# mcu.net
KiCad netlist of a schematic drawn in Altium Designer
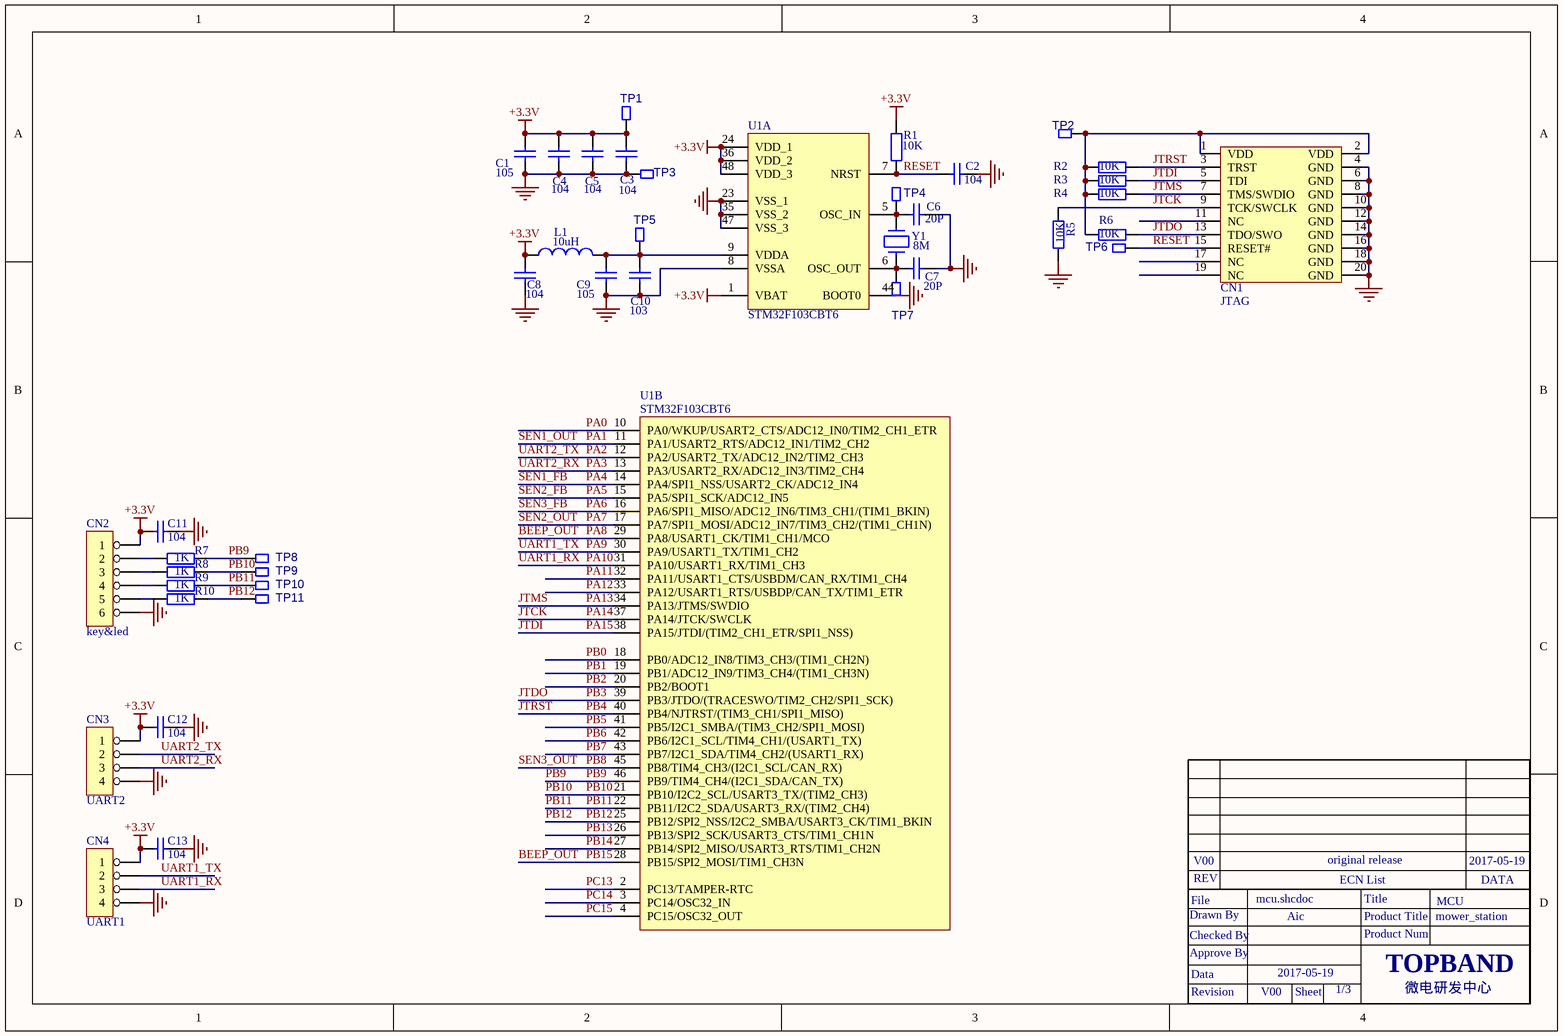
[diagram p0: mcu.SchDoc]

(export (version "E")
  (design (tool "Eeschema 10.0.6"))
  (components
    (comp (ref "C1")
      (value "105")
      (footprint "0603C")
      (libsource (lib "altium-import") (part "root_1_mirrored_Cap(0603)_"))
    )
    (comp (ref "C2")
      (value "104")
      (footprint "0603C")
      (libsource (lib "altium-import") (part "root_0_mirrored_Cap(0603)_"))
    )
    (comp (ref "C3")
      (value "104")
      (footprint "0603C")
      (libsource (lib "altium-import") (part "root_1_mirrored_Cap(0603)_"))
    )
    (comp (ref "C4")
      (value "104")
      (footprint "0603C")
      (libsource (lib "altium-import") (part "root_1_mirrored_Cap(0603)_"))
    )
    (comp (ref "C5")
      (value "104")
      (footprint "0603C")
      (libsource (lib "altium-import") (part "root_1_mirrored_Cap(0603)_"))
    )
    (comp (ref "C6")
      (value "20P")
      (footprint "0603C")
      (libsource (lib "altium-import") (part "root_0_mirrored_Cap(0603)_"))
    )
    (comp (ref "C7")
      (value "20P")
      (footprint "0603C")
      (libsource (lib "altium-import") (part "root_0_mirrored_Cap(0603)_"))
    )
    (comp (ref "C8")
      (value "104")
      (footprint "0603C")
      (libsource (lib "altium-import") (part "root_1_mirrored_Cap(0603)_"))
    )
    (comp (ref "C9")
      (value "105")
      (footprint "0603C")
      (libsource (lib "altium-import") (part "root_1_mirrored_Cap(0603)_"))
    )
    (comp (ref "C10")
      (value "103")
      (footprint "0603C")
      (libsource (lib "altium-import") (part "root_1_mirrored_Cap(0603)_"))
    )
    (comp (ref "C11")
      (value "104")
      (footprint "0603C")
      (libsource (lib "altium-import") (part "root_2_mirrored_Cap(0603)_"))
    )
    (comp (ref "C12")
      (value "104")
      (footprint "0603C")
      (libsource (lib "altium-import") (part "root_2_mirrored_Cap(0603)_"))
    )
    (comp (ref "C13")
      (value "104")
      (footprint "0603C")
      (libsource (lib "altium-import") (part "root_2_mirrored_Cap(0603)_"))
    )
    (comp (ref "CN1") (value "JTAG") (footprint "JTAG_20") (libsource (lib "STM32F429_F746") (part "JTAG")))
    (comp (ref "CN2")
      (value "key&led")
      (footprint "CON6-2.54")
      (description "插座")
      (fields (field (name "PART NUMBER") "6Pin"))
      (libsource (lib "接插器件+IC") (part "6Pin"))
    )
    (comp (ref "CN3")
      (value "UART2")
      (footprint "CON4-2.54")
      (description "插座")
      (fields (field (name "PART NUMBER") "4Pin(2~3.96mm)"))
      (libsource (lib "接插器件+IC") (part "4Pin(2~3.96mm)"))
    )
    (comp (ref "CN4")
      (value "UART1")
      (footprint "CON4-2.54")
      (description "插座")
      (fields (field (name "PART NUMBER") "4Pin(2~3.96mm)"))
      (libsource (lib "接插器件+IC") (part "4Pin(2~3.96mm)"))
    )
    (comp (ref "L1")
      (value "10uH")
      (footprint "0805L-BOT")
      (description "电感")
      (fields (field (name "PART NUMBER") "Inductor(0805)"))
      (libsource (lib "分立器件1") (part "Inductor(0805)"))
    )
    (comp (ref "R1")
      (value "10K")
      (footprint "0603R")
      (description "Resistor")
      (fields (field (name "PUBLISHER") "Altium Limited"))
      (libsource (lib "Miscellaneous Devices") (part "Res2"))
    )
    (comp (ref "R2")
      (value "10K")
      (footprint "0603R")
      (description "Resistor")
      (fields (field (name "PUBLISHER") "Altium Limited"))
      (libsource (lib "") (part "Res2_1"))
    )
    (comp (ref "R3")
      (value "10K")
      (footprint "0603R")
      (description "Resistor")
      (fields (field (name "PUBLISHER") "Altium Limited"))
      (libsource (lib "") (part "Res2_1"))
    )
    (comp (ref "R4")
      (value "10K")
      (footprint "0603R")
      (description "Resistor")
      (fields (field (name "PUBLISHER") "Altium Limited"))
      (libsource (lib "") (part "Res2_1"))
    )
    (comp (ref "R5")
      (value "10K")
      (footprint "0603R")
      (description "Resistor")
      (fields (field (name "PUBLISHER") "Altium Limited"))
      (libsource (lib "Miscellaneous Devices") (part "Res2"))
    )
    (comp (ref "R6")
      (value "10K")
      (footprint "0603R")
      (description "Resistor")
      (fields (field (name "PUBLISHER") "Altium Limited"))
      (libsource (lib "") (part "Res2_1"))
    )
    (comp (ref "R7")
      (value "1K")
      (footprint "0603R")
      (description "电阻器")
      (fields (field (name "PART NUMBER") "Res(0603)"))
      (libsource (lib "分立器件1") (part "Res(0603)"))
    )
    (comp (ref "R8")
      (value "1K")
      (footprint "0603R")
      (description "电阻器")
      (fields (field (name "PART NUMBER") "Res(0603)"))
      (libsource (lib "分立器件1") (part "Res(0603)"))
    )
    (comp (ref "R9")
      (value "1K")
      (footprint "0603R")
      (description "电阻器")
      (fields (field (name "PART NUMBER") "Res(0603)"))
      (libsource (lib "分立器件1") (part "Res(0603)"))
    )
    (comp (ref "R10")
      (value "1K")
      (footprint "0603R")
      (description "电阻器")
      (fields (field (name "PART NUMBER") "Res(0603)"))
      (libsource (lib "分立器件1") (part "Res(0603)"))
    )
    (comp (ref "TP1") (value "TP") (footprint "TEST-0.8MM") (libsource (lib "Topband1") (part "TP")))
    (comp (ref "TP2") (value "TP") (footprint "TEST-0.8MM") (libsource (lib "Topband1") (part "TP")))
    (comp (ref "TP3") (value "TP") (footprint "TEST-0.8MM") (libsource (lib "Topband1") (part "TP")))
    (comp (ref "TP4") (value "TP") (footprint "TEST-0.8MM") (libsource (lib "Topband1") (part "TP")))
    (comp (ref "TP5") (value "TP") (footprint "TEST-0.8MM") (libsource (lib "Topband1") (part "TP")))
    (comp (ref "TP6") (value "TP") (footprint "TEST-0.8MM") (libsource (lib "Topband1") (part "TP")))
    (comp (ref "TP7") (value "TP") (footprint "TEST-0.8MM") (libsource (lib "Topband1") (part "TP")))
    (comp (ref "TP8") (value "TP") (footprint "TEST-0.8MM") (libsource (lib "Topband1") (part "TP")))
    (comp (ref "TP9") (value "TP") (footprint "TEST-0.8MM") (libsource (lib "Topband1") (part "TP")))
    (comp (ref "TP10") (value "TP") (footprint "TEST-0.8MM") (libsource (lib "Topband1") (part "TP")))
    (comp (ref "TP11") (value "TP") (footprint "TEST-0.8MM") (libsource (lib "Topband1") (part "TP")))
    (comp (ref "U1")
      (value "STM32F103CBT6")
      (footprint "LQFP48")
      (description "STM32F103x8")
      (libsource (lib "Schlib1") (part "STM32F103x8"))
    )
    (comp (ref "Y1")
      (value "8M")
      (footprint "XTAL-J")
      (description "晶振")
      (fields (field (name "PART NUMBER") "XTAL-J"))
      (libsource (lib "分立器件1") (part "XTAL-J"))
    )
  )
  (nets
    (net (code "1") (name "+3.3V") (class "Default")
      (node (ref "C1") (pin "1") (pinfunction "1_1") (pintype "passive"))
      (node (ref "C11") (pin "1") (pinfunction "1_1") (pintype "passive"))
      (node (ref "C12") (pin "1") (pinfunction "1_1") (pintype "passive"))
      (node (ref "C13") (pin "1") (pinfunction "1_1") (pintype "passive"))
      (node (ref "C3") (pin "1") (pinfunction "1_1") (pintype "passive"))
      (node (ref "C4") (pin "1") (pinfunction "1_1") (pintype "passive"))
      (node (ref "C5") (pin "1") (pinfunction "1_1") (pintype "passive"))
      (node (ref "C8") (pin "1") (pinfunction "1_1") (pintype "passive"))
      (node (ref "CN2") (pin "1") (pinfunction "1_1") (pintype "passive"))
      (node (ref "CN3") (pin "1") (pinfunction "1_1") (pintype "passive"))
      (node (ref "CN4") (pin "1") (pinfunction "1_1") (pintype "passive"))
      (node (ref "L1") (pin "1") (pinfunction "1_1") (pintype "passive"))
      (node (ref "R1") (pin "1") (pinfunction "1_1") (pintype "passive"))
      (node (ref "TP1") (pin "1") (pintype "passive"))
      (node (ref "U1") (pin "1") (pinfunction "VBAT_1") (pintype "passive"))
      (node (ref "U1") (pin "24") (pinfunction "VDD_1_24") (pintype "passive"))
      (node (ref "U1") (pin "36") (pinfunction "VDD_2_36") (pintype "passive"))
      (node (ref "U1") (pin "48") (pinfunction "VDD_3_48") (pintype "passive"))
    )
    (net (code "2") (name "/BEEP_OUT") (class "Default")
      (node (ref "U1") (pin "28") (pinfunction "PB15/SPI2_MOSI/TIM1_CH3N_28") (pintype "passive"))
      (node (ref "U1") (pin "29") (pinfunction "PA8/USART1_CK/TIM1_CH1/MCO_29") (pintype "passive"))
    )
    (net (code "3") (name "/JTCK") (class "Default")
      (node (ref "CN1") (pin "9") (pinfunction "TCK/SWCLK_9") (pintype "passive"))
      (node (ref "R5") (pin "1") (pinfunction "1_1") (pintype "passive"))
      (node (ref "U1") (pin "37") (pinfunction "PA14/JTCK/SWCLK_37") (pintype "passive"))
    )
    (net (code "4") (name "/JTDI") (class "Default")
      (node (ref "CN1") (pin "5") (pinfunction "TDI_5") (pintype "passive"))
      (node (ref "R3") (pin "1") (pinfunction "1_1") (pintype "passive"))
      (node (ref "U1") (pin "38") (pinfunction "PA15/JTDI/(TIM2_CH1_ETR/SPI1_NSS)_38") (pintype "passive"))
    )
    (net (code "5") (name "/JTDO") (class "Default")
      (node (ref "CN1") (pin "13") (pinfunction "TDO/SWO_13") (pintype "passive"))
      (node (ref "R6") (pin "1") (pinfunction "1_1") (pintype "passive"))
      (node (ref "U1") (pin "39") (pinfunction "PB3/JTDO/(TRACESWO/TIM2_CH2/SPI1_SCK)_39") (pintype "passive"))
    )
    (net (code "6") (name "/JTMS") (class "Default")
      (node (ref "CN1") (pin "7") (pinfunction "TMS/SWDIO_7") (pintype "passive"))
      (node (ref "R4") (pin "1") (pinfunction "1_1") (pintype "passive"))
      (node (ref "U1") (pin "34") (pinfunction "PA13/JTMS/SWDIO_34") (pintype "passive"))
    )
    (net (code "7") (name "/JTRST") (class "Default")
      (node (ref "CN1") (pin "3") (pinfunction "TRST_3") (pintype "passive"))
      (node (ref "R2") (pin "1") (pinfunction "1_1") (pintype "passive"))
      (node (ref "U1") (pin "40") (pinfunction "PB4/NJTRST/(TIM3_CH1/SPI1_MISO)_40") (pintype "passive"))
    )
    (net (code "8") (name "/PA0") (class "Default")
      (node (ref "U1") (pin "10") (pinfunction "PA0/WKUP/USART2_CTS/ADC12_IN0/TIM2_CH1_ETR_10") (pintype "passive"))
    )
    (net (code "9") (name "/PA1") (class "Default")
      (node (ref "U1") (pin "11") (pinfunction "PA1/USART2_RTS/ADC12_IN1/TIM2_CH2_11") (pintype "passive"))
    )
    (net (code "10") (name "/PA2") (class "Default")
      (node (ref "CN3") (pin "2") (pinfunction "2_2") (pintype "passive"))
      (node (ref "U1") (pin "12") (pinfunction "PA2/USART2_TX/ADC12_IN2/TIM2_CH3_12") (pintype "passive"))
    )
    (net (code "11") (name "/PA3") (class "Default")
      (node (ref "CN3") (pin "3") (pinfunction "3_3") (pintype "passive"))
      (node (ref "U1") (pin "13") (pinfunction "PA3/USART2_RX/ADC12_IN3/TIM2_CH4_13") (pintype "passive"))
    )
    (net (code "12") (name "/PA4") (class "Default")
      (node (ref "U1") (pin "14") (pinfunction "PA4/SPI1_NSS/USART2_CK/ADC12_IN4_14") (pintype "passive"))
    )
    (net (code "13") (name "/PA5") (class "Default")
      (node (ref "U1") (pin "15") (pinfunction "PA5/SPI1_SCK/ADC12_IN5_15") (pintype "passive"))
    )
    (net (code "14") (name "/PA6") (class "Default")
      (node (ref "U1") (pin "16") (pinfunction "PA6/SPI1_MISO/ADC12_IN6/TIM3_CH1/(TIM1_BKIN)_16") (pintype "passive"))
    )
    (net (code "15") (name "/PA7") (class "Default")
      (node (ref "U1") (pin "17") (pinfunction "PA7/SPI1_MOSI/ADC12_IN7/TIM3_CH2/(TIM1_CH1N)_17") (pintype "passive"))
    )
    (net (code "16") (name "/PA9") (class "Default")
      (node (ref "CN4") (pin "2") (pinfunction "2_2") (pintype "passive"))
      (node (ref "U1") (pin "30") (pinfunction "PA9/USART1_TX/TIM1_CH2_30") (pintype "passive"))
    )
    (net (code "17") (name "/PA10") (class "Default")
      (node (ref "CN4") (pin "3") (pinfunction "3_3") (pintype "passive"))
      (node (ref "U1") (pin "31") (pinfunction "PA10/USART1_RX/TIM1_CH3_31") (pintype "passive"))
    )
    (net (code "18") (name "/PA11") (class "Default")
      (node (ref "U1") (pin "32") (pinfunction "PA11/USART1_CTS/USBDM/CAN_RX/TIM1_CH4_32") (pintype "passive"))
    )
    (net (code "19") (name "/PA12") (class "Default")
      (node (ref "U1") (pin "33") (pinfunction "PA12/USART1_RTS/USBDP/CAN_TX/TIM1_ETR_33") (pintype "passive"))
    )
    (net (code "20") (name "/PB0") (class "Default")
      (node (ref "U1") (pin "18") (pinfunction "PB0/ADC12_IN8/TIM3_CH3/(TIM1_CH2N)_18") (pintype "passive"))
    )
    (net (code "21") (name "/PB1") (class "Default")
      (node (ref "U1") (pin "19") (pinfunction "PB1/ADC12_IN9/TIM3_CH4/(TIM1_CH3N)_19") (pintype "passive"))
    )
    (net (code "22") (name "/PB2") (class "Default")
      (node (ref "U1") (pin "20") (pinfunction "PB2/BOOT1_20") (pintype "passive"))
    )
    (net (code "23") (name "/PB5") (class "Default")
      (node (ref "U1") (pin "41") (pinfunction "PB5/I2C1_SMBA/(TIM3_CH2/SPI1_MOSI)_41") (pintype "passive"))
    )
    (net (code "24") (name "/PB6") (class "Default")
      (node (ref "U1") (pin "42") (pinfunction "PB6/I2C1_SCL/TIM4_CH1/(USART1_TX)_42") (pintype "passive"))
    )
    (net (code "25") (name "/PB7") (class "Default")
      (node (ref "U1") (pin "43") (pinfunction "PB7/I2C1_SDA/TIM4_CH2/(USART1_RX)_43") (pintype "passive"))
    )
    (net (code "26") (name "/PB8") (class "Default")
      (node (ref "U1") (pin "45") (pinfunction "PB8/TIM4_CH3/(I2C1_SCL/CAN_RX)_45") (pintype "passive"))
    )
    (net (code "27") (name "/PB9") (class "Default")
      (node (ref "R7") (pin "2") (pinfunction "2_2") (pintype "passive"))
      (node (ref "TP8") (pin "1") (pintype "passive"))
      (node (ref "U1") (pin "46") (pinfunction "PB9/TIM4_CH4/(I2C1_SDA/CAN_TX)_46") (pintype "passive"))
    )
    (net (code "28") (name "/PB10") (class "Default")
      (node (ref "R8") (pin "2") (pinfunction "2_2") (pintype "passive"))
      (node (ref "TP9") (pin "1") (pintype "passive"))
      (node (ref "U1") (pin "21") (pinfunction "PB10/I2C2_SCL/USART3_TX/(TIM2_CH3)_21") (pintype "passive"))
    )
    (net (code "29") (name "/PB11") (class "Default")
      (node (ref "R9") (pin "2") (pinfunction "2_2") (pintype "passive"))
      (node (ref "TP10") (pin "1") (pintype "passive"))
      (node (ref "U1") (pin "22") (pinfunction "PB11/I2C2_SDA/USART3_RX/(TIM2_CH4)_22") (pintype "passive"))
    )
    (net (code "30") (name "/PB12") (class "Default")
      (node (ref "R10") (pin "2") (pinfunction "2_2") (pintype "passive"))
      (node (ref "TP11") (pin "1") (pintype "passive"))
      (node (ref "U1") (pin "25") (pinfunction "PB12/SPI2_NSS/I2C2_SMBA/USART3_CK/TIM1_BKIN_25") (pintype "passive"))
    )
    (net (code "31") (name "/PB13") (class "Default")
      (node (ref "U1") (pin "26") (pinfunction "PB13/SPI2_SCK/USART3_CTS/TIM1_CH1N_26") (pintype "passive"))
    )
    (net (code "32") (name "/PB14") (class "Default")
      (node (ref "U1") (pin "27") (pinfunction "PB14/SPI2_MISO/USART3_RTS/TIM1_CH2N_27") (pintype "passive"))
    )
    (net (code "33") (name "/PC13") (class "Default")
      (node (ref "U1") (pin "2") (pinfunction "PC13/TAMPER-RTC_2") (pintype "passive"))
    )
    (net (code "34") (name "/PC14") (class "Default")
      (node (ref "U1") (pin "3") (pinfunction "PC14/OSC32_IN_3") (pintype "passive"))
    )
    (net (code "35") (name "/PC15") (class "Default")
      (node (ref "U1") (pin "4") (pinfunction "PC15/OSC32_OUT_4") (pintype "passive"))
    )
    (net (code "36") (name "/RESET") (class "Default")
      (node (ref "C2") (pin "2") (pinfunction "2_2") (pintype "passive"))
      (node (ref "CN1") (pin "15") (pinfunction "RESET#_15") (pintype "passive"))
      (node (ref "R1") (pin "2") (pinfunction "2_2") (pintype "passive"))
      (node (ref "TP6") (pin "1") (pintype "passive"))
      (node (ref "U1") (pin "7") (pinfunction "NRST_7") (pintype "passive"))
    )
    (net (code "37") (name "GND") (class "Default")
      (node (ref "C1") (pin "2") (pinfunction "2_2") (pintype "passive"))
      (node (ref "C10") (pin "2") (pinfunction "2_2") (pintype "passive"))
      (node (ref "C11") (pin "2") (pinfunction "2_2") (pintype "passive"))
      (node (ref "C12") (pin "2") (pinfunction "2_2") (pintype "passive"))
      (node (ref "C13") (pin "2") (pinfunction "2_2") (pintype "passive"))
      (node (ref "C2") (pin "1") (pinfunction "1_1") (pintype "passive"))
      (node (ref "C3") (pin "2") (pinfunction "2_2") (pintype "passive"))
      (node (ref "C4") (pin "2") (pinfunction "2_2") (pintype "passive"))
      (node (ref "C5") (pin "2") (pinfunction "2_2") (pintype "passive"))
      (node (ref "C6") (pin "1") (pinfunction "1_1") (pintype "passive"))
      (node (ref "C7") (pin "1") (pinfunction "1_1") (pintype "passive"))
      (node (ref "C8") (pin "2") (pinfunction "2_2") (pintype "passive"))
      (node (ref "C9") (pin "2") (pinfunction "2_2") (pintype "passive"))
      (node (ref "CN1") (pin "10") (pinfunction "GND_10") (pintype "passive"))
      (node (ref "CN1") (pin "12") (pinfunction "GND_12") (pintype "passive"))
      (node (ref "CN1") (pin "14") (pinfunction "GND_14") (pintype "passive"))
      (node (ref "CN1") (pin "16") (pinfunction "GND_16") (pintype "passive"))
      (node (ref "CN1") (pin "18") (pinfunction "GND_18") (pintype "passive"))
      (node (ref "CN1") (pin "20") (pinfunction "GND_20") (pintype "passive"))
      (node (ref "CN1") (pin "4") (pinfunction "GND_4") (pintype "passive"))
      (node (ref "CN1") (pin "6") (pinfunction "GND_6") (pintype "passive"))
      (node (ref "CN1") (pin "8") (pinfunction "GND_8") (pintype "passive"))
      (node (ref "CN2") (pin "6") (pinfunction "6_6") (pintype "passive"))
      (node (ref "CN3") (pin "4") (pinfunction "4_4") (pintype "passive"))
      (node (ref "CN4") (pin "4") (pinfunction "4_4") (pintype "passive"))
      (node (ref "R5") (pin "2") (pinfunction "2_2") (pintype "passive"))
      (node (ref "TP3") (pin "1") (pintype "passive"))
      (node (ref "U1") (pin "23") (pinfunction "VSS_1_23") (pintype "passive"))
      (node (ref "U1") (pin "35") (pinfunction "VSS_2_35") (pintype "passive"))
      (node (ref "U1") (pin "44") (pinfunction "BOOT0_44") (pintype "passive"))
      (node (ref "U1") (pin "47") (pinfunction "VSS_3_47") (pintype "passive"))
      (node (ref "U1") (pin "8") (pinfunction "VSSA_8") (pintype "passive"))
    )
    (net (code "38") (name "Net-(CN1-VDD-Pad1)") (class "Default")
      (node (ref "CN1") (pin "1") (pinfunction "VDD_1") (pintype "passive"))
      (node (ref "CN1") (pin "2") (pinfunction "VDD_2") (pintype "passive"))
      (node (ref "R2") (pin "2") (pinfunction "2_2") (pintype "passive"))
      (node (ref "R3") (pin "2") (pinfunction "2_2") (pintype "passive"))
      (node (ref "R4") (pin "2") (pinfunction "2_2") (pintype "passive"))
      (node (ref "R6") (pin "2") (pinfunction "2_2") (pintype "passive"))
      (node (ref "TP2") (pin "1") (pintype "passive"))
    )
    (net (code "39") (name "Net-(CN2-Pad2)") (class "Default")
      (node (ref "CN2") (pin "2") (pinfunction "2_2") (pintype "passive"))
      (node (ref "R7") (pin "1") (pinfunction "1_1") (pintype "passive"))
    )
    (net (code "40") (name "Net-(CN2-Pad3)") (class "Default")
      (node (ref "CN2") (pin "3") (pinfunction "3_3") (pintype "passive"))
      (node (ref "R8") (pin "1") (pinfunction "1_1") (pintype "passive"))
    )
    (net (code "41") (name "Net-(CN2-Pad4)") (class "Default")
      (node (ref "CN2") (pin "4") (pinfunction "4_4") (pintype "passive"))
      (node (ref "R9") (pin "1") (pinfunction "1_1") (pintype "passive"))
    )
    (net (code "42") (name "Net-(CN2-Pad5)") (class "Default")
      (node (ref "CN2") (pin "5") (pinfunction "5_5") (pintype "passive"))
      (node (ref "R10") (pin "1") (pinfunction "1_1") (pintype "passive"))
    )
    (net (code "43") (name "Net-(U1A-OSC_IN)") (class "Default")
      (node (ref "C6") (pin "2") (pinfunction "2_2") (pintype "passive"))
      (node (ref "TP4") (pin "1") (pintype "passive"))
      (node (ref "U1") (pin "5") (pinfunction "OSC_IN_5") (pintype "passive"))
      (node (ref "Y1") (pin "2") (pinfunction "2_2") (pintype "passive"))
    )
    (net (code "44") (name "Net-(U1A-OSC_OUT)") (class "Default")
      (node (ref "C7") (pin "2") (pinfunction "2_2") (pintype "passive"))
      (node (ref "TP7") (pin "1") (pintype "passive"))
      (node (ref "U1") (pin "6") (pinfunction "OSC_OUT_6") (pintype "passive"))
      (node (ref "Y1") (pin "1") (pinfunction "1_1") (pintype "passive"))
    )
    (net (code "45") (name "Net-(U1A-VDDA)") (class "Default")
      (node (ref "C10") (pin "1") (pinfunction "1_1") (pintype "passive"))
      (node (ref "C9") (pin "1") (pinfunction "1_1") (pintype "passive"))
      (node (ref "L1") (pin "2") (pinfunction "2_2") (pintype "passive"))
      (node (ref "TP5") (pin "1") (pintype "passive"))
      (node (ref "U1") (pin "9") (pinfunction "VDDA_9") (pintype "passive"))
    )
    (net (code "46") (name "unconnected-(CN1-NC-Pad11)") (class "Default")
      (node (ref "CN1") (pin "11") (pinfunction "NC_11") (pintype "passive"))
    )
    (net (code "47") (name "unconnected-(CN1-NC-Pad17)") (class "Default")
      (node (ref "CN1") (pin "17") (pinfunction "NC_17") (pintype "passive"))
    )
    (net (code "48") (name "unconnected-(CN1-NC-Pad19)") (class "Default")
      (node (ref "CN1") (pin "19") (pinfunction "NC_19") (pintype "passive"))
    )
  )
)
